# Power_module_12V_to_5V.net
KiCad netlist of a schematic drawn in EAGLE
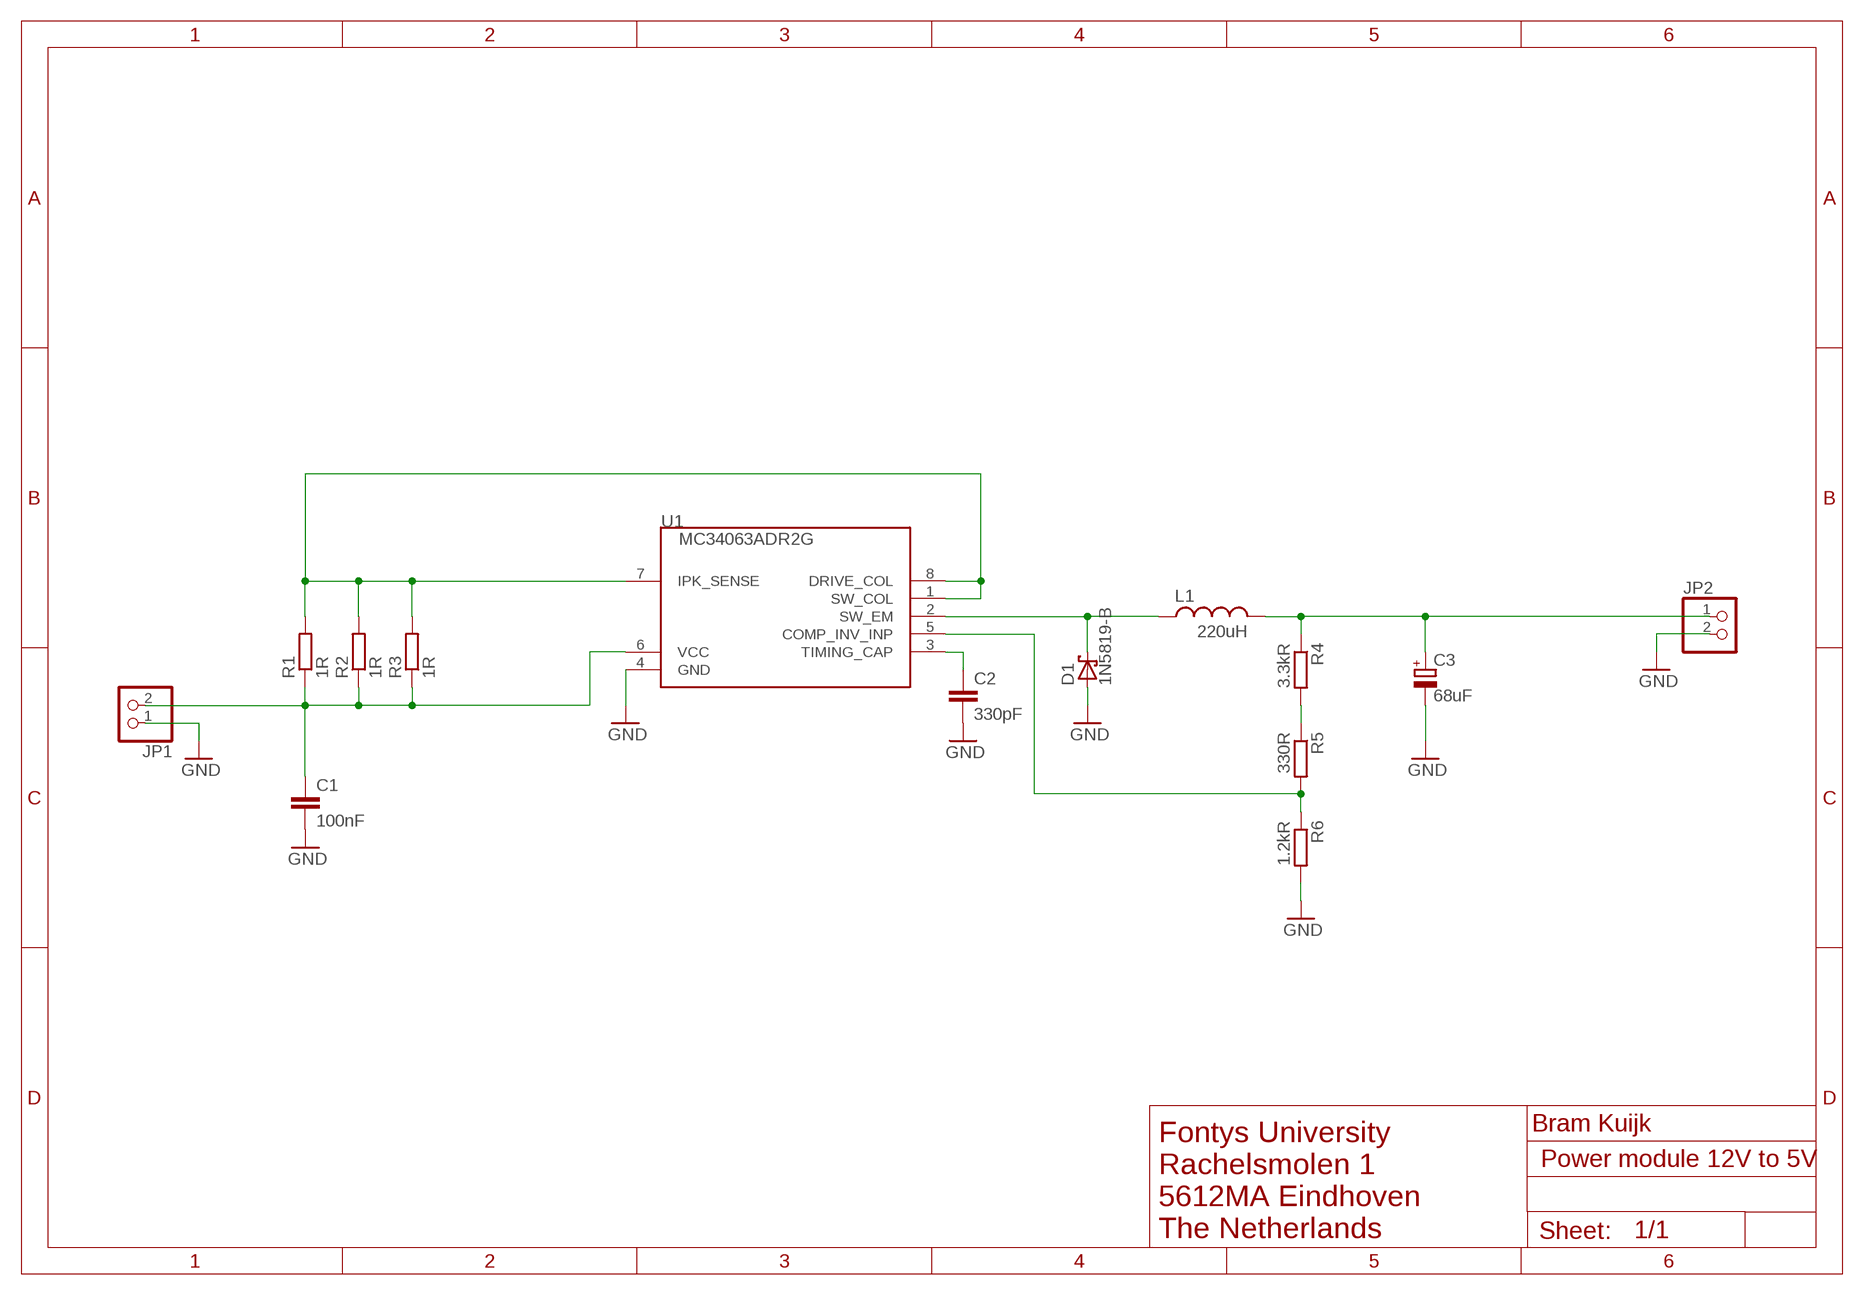
[diagram p0: schematic, sheet 1]

(export (version "E")
  (design (tool "Eeschema 10.0.6"))
  (components
    (comp (ref "C1")
      (value "100nF")
      (footprint "eagle-import:C050-045X075")
      (libsource (lib "eagle-import") (part "C-EU050-045X075"))
    )
    (comp (ref "C2")
      (value "330pF")
      (footprint "eagle-import:C050-045X075")
      (libsource (lib "eagle-import") (part "C-EU050-045X075"))
    )
    (comp (ref "C3")
      (value "68uF")
      (footprint "eagle-import:E2,5-7")
      (libsource (lib "eagle-import") (part "CPOL-EUE2.5-7"))
    )
    (comp (ref "D1")
      (value "1N5819-B")
      (footprint "eagle-import:DO41-7.6")
      (libsource (lib "eagle-import") (part "1N5819-B"))
    )
    (comp (ref "JP1")
      (value "PINHD-1X2")
      (footprint "eagle-import:1X02")
      (libsource (lib "eagle-import") (part "PINHD-1X2"))
    )
    (comp (ref "JP2")
      (value "PINHD-1X2")
      (footprint "eagle-import:1X02")
      (libsource (lib "eagle-import") (part "PINHD-1X2"))
    )
    (comp (ref "L1")
      (value "220uH")
      (footprint "eagle-import:SRR1208_L")
      (libsource (lib "eagle-import") (part "SRR1208"))
    )
    (comp (ref "R1")
      (value "1R")
      (footprint "eagle-import:0207_10")
      (libsource (lib "eagle-import") (part "R-EU_0207/10"))
    )
    (comp (ref "R2")
      (value "1R")
      (footprint "eagle-import:0207_10")
      (libsource (lib "eagle-import") (part "R-EU_0207/10"))
    )
    (comp (ref "R3")
      (value "1R")
      (footprint "eagle-import:0207_10")
      (libsource (lib "eagle-import") (part "R-EU_0207/10"))
    )
    (comp (ref "R4")
      (value "3.3kR")
      (footprint "eagle-import:0207_10")
      (libsource (lib "eagle-import") (part "R-EU_0207/10"))
    )
    (comp (ref "R5")
      (value "330R")
      (footprint "eagle-import:0207_10")
      (libsource (lib "eagle-import") (part "R-EU_0207/10"))
    )
    (comp (ref "R6")
      (value "1.2kR")
      (footprint "eagle-import:0207_10")
      (libsource (lib "eagle-import") (part "R-EU_0207/10"))
    )
    (comp (ref "U1")
      (value "MC34063ADR2G")
      (footprint "eagle-import:SOIC8")
      (libsource (lib "eagle-import") (part "MC34063ADR2G"))
    )
  )
  (nets
    (net (code "1") (name "GND") (class "Default")
      (node (ref "C1") (pin "2") (pinfunction "2_2") (pintype "passive"))
      (node (ref "C2") (pin "2") (pinfunction "2_2") (pintype "passive"))
      (node (ref "C3") (pin "-") (pinfunction "-_-") (pintype "passive"))
      (node (ref "D1") (pin "A") (pinfunction "A_A") (pintype "passive"))
      (node (ref "JP1") (pin "1") (pinfunction "1_1") (pintype "passive"))
      (node (ref "JP2") (pin "2") (pinfunction "2_2") (pintype "passive"))
      (node (ref "R6") (pin "2") (pinfunction "2_2") (pintype "passive"))
      (node (ref "U1") (pin "4") (pinfunction "GND_4") (pintype "bidirectional"))
    )
    (net (code "2") (name "Net-(L1-1)") (class "Default")
      (node (ref "D1") (pin "C") (pinfunction "C_C") (pintype "passive"))
      (node (ref "L1") (pin "P$1") (pinfunction "1_P$1") (pintype "passive"))
      (node (ref "U1") (pin "2") (pinfunction "SW_EM_2") (pintype "bidirectional"))
    )
    (net (code "3") (name "Net-(L1-2)") (class "Default")
      (node (ref "C3") (pin "+") (pinfunction "+_+") (pintype "passive"))
      (node (ref "JP2") (pin "1") (pinfunction "1_1") (pintype "passive"))
      (node (ref "L1") (pin "P$2") (pinfunction "2_P$2") (pintype "passive"))
      (node (ref "R4") (pin "1") (pinfunction "1_1") (pintype "passive"))
    )
    (net (code "4") (name "Net-(R4-Pad2)") (class "Default")
      (node (ref "R4") (pin "2") (pinfunction "2_2") (pintype "passive"))
      (node (ref "R5") (pin "1") (pinfunction "1_1") (pintype "passive"))
    )
    (net (code "5") (name "Net-(U1-COMP_INV_INP)") (class "Default")
      (node (ref "R5") (pin "2") (pinfunction "2_2") (pintype "passive"))
      (node (ref "R6") (pin "1") (pinfunction "1_1") (pintype "passive"))
      (node (ref "U1") (pin "5") (pinfunction "COMP_INV_INP_5") (pintype "bidirectional"))
    )
    (net (code "6") (name "Net-(U1-DRIVE_COL)") (class "Default")
      (node (ref "R1") (pin "2") (pinfunction "2_2") (pintype "passive"))
      (node (ref "R2") (pin "2") (pinfunction "2_2") (pintype "passive"))
      (node (ref "R3") (pin "2") (pinfunction "2_2") (pintype "passive"))
      (node (ref "U1") (pin "1") (pinfunction "SW_COL_1") (pintype "bidirectional"))
      (node (ref "U1") (pin "7") (pinfunction "IPK_SENSE_7") (pintype "bidirectional"))
      (node (ref "U1") (pin "8") (pinfunction "DRIVE_COL_8") (pintype "bidirectional"))
    )
    (net (code "7") (name "Net-(U1-TIMING_CAP)") (class "Default")
      (node (ref "C2") (pin "1") (pinfunction "1_1") (pintype "passive"))
      (node (ref "U1") (pin "3") (pinfunction "TIMING_CAP_3") (pintype "bidirectional"))
    )
    (net (code "8") (name "Net-(U1-VCC)") (class "Default")
      (node (ref "C1") (pin "1") (pinfunction "1_1") (pintype "passive"))
      (node (ref "JP1") (pin "2") (pinfunction "2_2") (pintype "passive"))
      (node (ref "R1") (pin "1") (pinfunction "1_1") (pintype "passive"))
      (node (ref "R2") (pin "1") (pinfunction "1_1") (pintype "passive"))
      (node (ref "R3") (pin "1") (pinfunction "1_1") (pintype "passive"))
      (node (ref "U1") (pin "6") (pinfunction "VCC_6") (pintype "bidirectional"))
    )
  )
)
